# tft.net
KiCad netlist of a schematic drawn in EAGLE
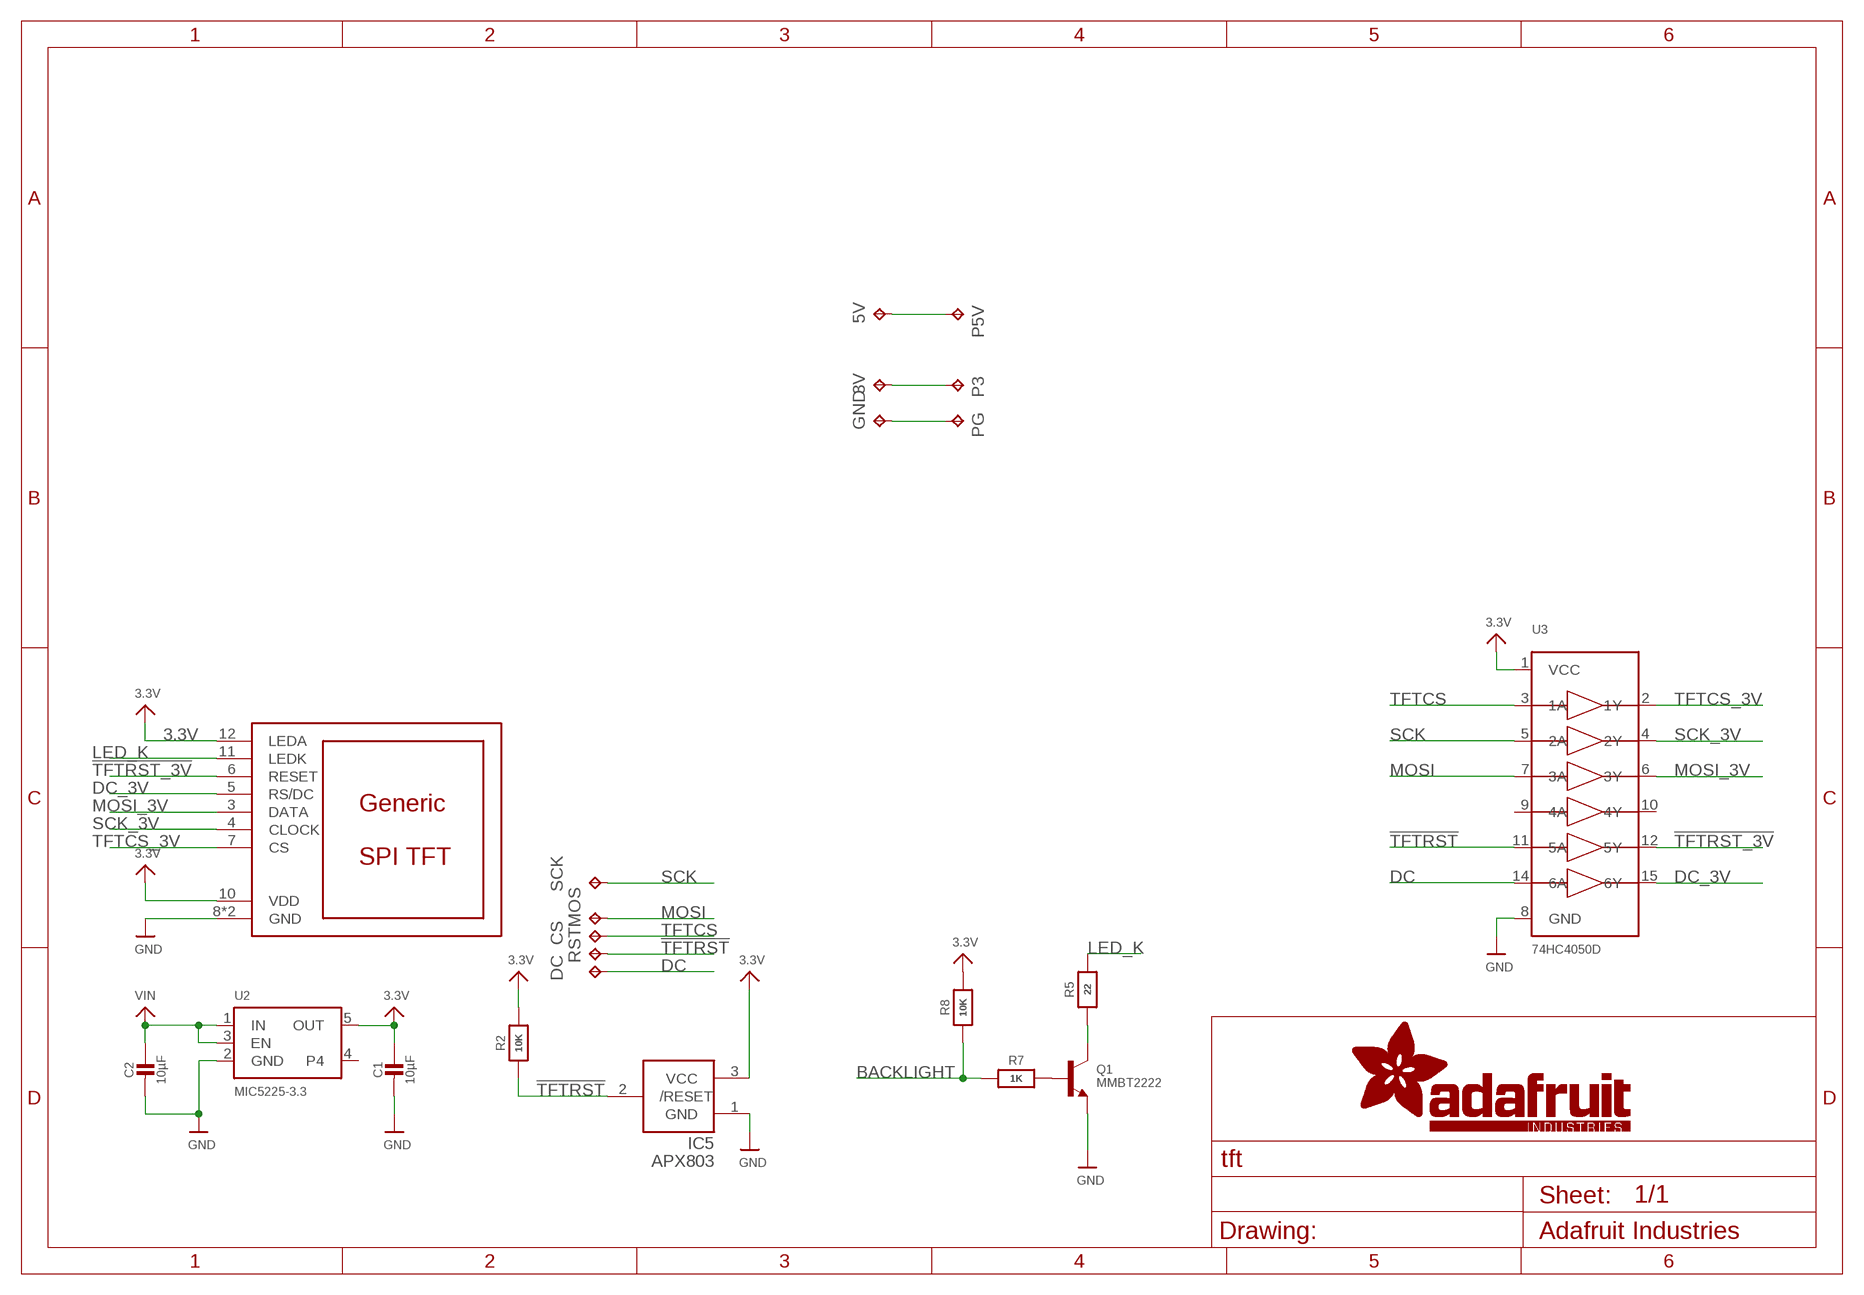
[diagram p0: schematic, sheet 1]

(export (version "E")
  (design (tool "Eeschema 10.0.6"))
  (components
    (comp (ref "3V")
      (value "TPB1,27")
      (footprint "eagle-import:B1,27")
      (libsource (lib "eagle-import") (part "TPB1,27"))
    )
    (comp (ref "5V")
      (value "TPB1,27")
      (footprint "eagle-import:B1,27")
      (libsource (lib "eagle-import") (part "TPB1,27"))
    )
    (comp (ref "C1")
      (value "10µF")
      (footprint "eagle-import:0805-NO")
      (libsource (lib "eagle-import") (part "CAP_CERAMIC0805-NOOUTLINE"))
    )
    (comp (ref "C2")
      (value "10µF")
      (footprint "eagle-import:0805-NO")
      (libsource (lib "eagle-import") (part "CAP_CERAMIC0805-NOOUTLINE"))
    )
    (comp (ref "CS")
      (value "TPB1,27")
      (footprint "eagle-import:B1,27")
      (libsource (lib "eagle-import") (part "TPB1,27"))
    )
    (comp (ref "DC")
      (value "TPB1,27")
      (footprint "eagle-import:B1,27")
      (libsource (lib "eagle-import") (part "TPB1,27"))
    )
    (comp (ref "DISP1")
      (value "DISP_LCD_GENERIC_SPI_1.14IN_240X135_WRAPUNDER")
      (footprint "eagle-import:TFT_1.14IN_240X135_WRAPUNDER")
      (libsource (lib "eagle-import") (part "DISP_LCD_GENERIC_SPI_1.14IN_240X135_WRAPUNDER"))
    )
    (comp (ref "GND")
      (value "TPB1,27")
      (footprint "eagle-import:B1,27")
      (libsource (lib "eagle-import") (part "TPB1,27"))
    )
    (comp (ref "IC5")
      (value "APX803")
      (footprint "eagle-import:SOT23")
      (libsource (lib "eagle-import") (part "AXP083-SAG"))
    )
    (comp (ref "MOS")
      (value "TPB1,27")
      (footprint "eagle-import:B1,27")
      (libsource (lib "eagle-import") (part "TPB1,27"))
    )
    (comp (ref "P3")
      (value "TPB1,27")
      (footprint "eagle-import:B1,27")
      (libsource (lib "eagle-import") (part "TPB1,27"))
    )
    (comp (ref "P5V")
      (value "TPB1,27")
      (footprint "eagle-import:B1,27")
      (libsource (lib "eagle-import") (part "TPB1,27"))
    )
    (comp (ref "PG")
      (value "TPB1,27")
      (footprint "eagle-import:B1,27")
      (libsource (lib "eagle-import") (part "TPB1,27"))
    )
    (comp (ref "Q1")
      (value "MMBT2222")
      (footprint "eagle-import:SOT23-WIDE")
      (libsource (lib "eagle-import") (part "TRANSISTOR_NPNWIDE"))
    )
    (comp (ref "R2")
      (value "10K")
      (footprint "eagle-import:0603-NO")
      (libsource (lib "eagle-import") (part "RESISTOR_0603_NOOUT"))
    )
    (comp (ref "R5")
      (value "22")
      (footprint "eagle-import:0603-NO")
      (libsource (lib "eagle-import") (part "RESISTOR_0603_NOOUT"))
    )
    (comp (ref "R7")
      (value "1K")
      (footprint "eagle-import:0603-NO")
      (libsource (lib "eagle-import") (part "RESISTOR_0603_NOOUT"))
    )
    (comp (ref "R8")
      (value "10K")
      (footprint "eagle-import:0603-NO")
      (libsource (lib "eagle-import") (part "RESISTOR_0603_NOOUT"))
    )
    (comp (ref "RST")
      (value "TPB1,27")
      (footprint "eagle-import:B1,27")
      (libsource (lib "eagle-import") (part "TPB1,27"))
    )
    (comp (ref "SCK")
      (value "TPB1,27")
      (footprint "eagle-import:B1,27")
      (libsource (lib "eagle-import") (part "TPB1,27"))
    )
    (comp (ref "U2")
      (value "MIC5225-3.3")
      (footprint "eagle-import:SOT23-5")
      (libsource (lib "eagle-import") (part "VREG_SOT23-5"))
    )
    (comp (ref "U3")
      (value "74HC4050D")
      (footprint "eagle-import:SOIC16")
      (libsource (lib "eagle-import") (part "74HC4050D"))
    )
  )
  (nets
    (net (code "1") (name "/BACKLIGHT") (class "Default")
      (node (ref "R7") (pin "1") (pinfunction "1_1") (pintype "passive"))
      (node (ref "R8") (pin "1") (pinfunction "1_1") (pintype "passive"))
    )
    (net (code "2") (name "/DC") (class "Default")
      (node (ref "DC") (pin "TP") (pinfunction "TP_TP") (pintype "input"))
      (node (ref "U3") (pin "14") (pinfunction "6A_14") (pintype "bidirectional"))
    )
    (net (code "3") (name "/DC_3V") (class "Default")
      (node (ref "DISP1") (pin "5") (pinfunction "RS/DC_5") (pintype "input"))
      (node (ref "U3") (pin "15") (pinfunction "6Y_15") (pintype "bidirectional"))
    )
    (net (code "4") (name "/LED_K") (class "Default")
      (node (ref "DISP1") (pin "11") (pinfunction "LEDK_11") (pintype "input"))
      (node (ref "R5") (pin "2") (pinfunction "2_2") (pintype "passive"))
    )
    (net (code "5") (name "/MOSI") (class "Default")
      (node (ref "MOS") (pin "TP") (pinfunction "TP_TP") (pintype "input"))
      (node (ref "U3") (pin "7") (pinfunction "3A_7") (pintype "bidirectional"))
    )
    (net (code "6") (name "/MOSI_3V") (class "Default")
      (node (ref "DISP1") (pin "3") (pinfunction "DATA_3") (pintype "bidirectional"))
      (node (ref "U3") (pin "6") (pinfunction "3Y_6") (pintype "bidirectional"))
    )
    (net (code "7") (name "/SCK") (class "Default")
      (node (ref "SCK") (pin "TP") (pinfunction "TP_TP") (pintype "input"))
      (node (ref "U3") (pin "5") (pinfunction "2A_5") (pintype "bidirectional"))
    )
    (net (code "8") (name "/SCK_3V") (class "Default")
      (node (ref "DISP1") (pin "4") (pinfunction "CLOCK_4") (pintype "input"))
      (node (ref "U3") (pin "4") (pinfunction "2Y_4") (pintype "bidirectional"))
    )
    (net (code "9") (name "/TFTCS") (class "Default")
      (node (ref "CS") (pin "TP") (pinfunction "TP_TP") (pintype "input"))
      (node (ref "U3") (pin "3") (pinfunction "1A_3") (pintype "bidirectional"))
    )
    (net (code "10") (name "/TFTCS_3V") (class "Default")
      (node (ref "DISP1") (pin "7") (pinfunction "CS_7") (pintype "input"))
      (node (ref "U3") (pin "2") (pinfunction "1Y_2") (pintype "bidirectional"))
    )
    (net (code "11") (name "/~{TFTRST_3V}") (class "Default")
      (node (ref "DISP1") (pin "6") (pinfunction "RESET_6") (pintype "input"))
      (node (ref "U3") (pin "12") (pinfunction "5Y_12") (pintype "bidirectional"))
    )
    (net (code "12") (name "/~{TFTRST}") (class "Default")
      (node (ref "IC5") (pin "2") (pinfunction "/RESET_2") (pintype "output"))
      (node (ref "R2") (pin "1") (pinfunction "1_1") (pintype "passive"))
      (node (ref "RST") (pin "TP") (pinfunction "TP_TP") (pintype "input"))
      (node (ref "U3") (pin "11") (pinfunction "5A_11") (pintype "bidirectional"))
    )
    (net (code "13") (name "3.3V") (class "Default")
      (node (ref "C1") (pin "1") (pinfunction "1_1") (pintype "passive"))
      (node (ref "DISP1") (pin "10") (pinfunction "VDD_10") (pintype "power_in"))
      (node (ref "DISP1") (pin "12") (pinfunction "LEDA_12") (pintype "input"))
      (node (ref "IC5") (pin "3") (pinfunction "VCC_3") (pintype "power_in"))
      (node (ref "R2") (pin "2") (pinfunction "2_2") (pintype "passive"))
      (node (ref "R8") (pin "2") (pinfunction "2_2") (pintype "passive"))
      (node (ref "U2") (pin "5") (pinfunction "OUT_5") (pintype "power_in"))
      (node (ref "U3") (pin "1") (pinfunction "VCC_1") (pintype "bidirectional"))
    )
    (net (code "14") (name "GND") (class "Default")
      (node (ref "C1") (pin "2") (pinfunction "2_2") (pintype "passive"))
      (node (ref "C2") (pin "2") (pinfunction "2_2") (pintype "passive"))
      (node (ref "DISP1") (pin "13") (pinfunction "GND_13") (pintype "power_in"))
      (node (ref "DISP1") (pin "8") (pinfunction "GND_8") (pintype "power_in"))
      (node (ref "GND") (pin "TP") (pinfunction "TP_TP") (pintype "input"))
      (node (ref "IC5") (pin "1") (pinfunction "GND_1") (pintype "power_in"))
      (node (ref "PG") (pin "TP") (pinfunction "TP_TP") (pintype "input"))
      (node (ref "Q1") (pin "2") (pinfunction "E_2") (pintype "passive"))
      (node (ref "U2") (pin "2") (pinfunction "GND_2") (pintype "power_in"))
      (node (ref "U3") (pin "8") (pinfunction "GND_8") (pintype "bidirectional"))
    )
    (net (code "15") (name "Net-(5V-PadTP)") (class "Default")
      (node (ref "5V") (pin "TP") (pinfunction "TP_TP") (pintype "input"))
      (node (ref "P5V") (pin "TP") (pinfunction "TP_TP") (pintype "input"))
    )
    (net (code "16") (name "Net-(Q1-B)") (class "Default")
      (node (ref "Q1") (pin "1") (pinfunction "B_1") (pintype "passive"))
      (node (ref "R7") (pin "2") (pinfunction "2_2") (pintype "passive"))
    )
    (net (code "17") (name "Net-(Q1-C)") (class "Default")
      (node (ref "Q1") (pin "3") (pinfunction "C_3") (pintype "passive"))
      (node (ref "R5") (pin "1") (pinfunction "1_1") (pintype "passive"))
    )
    (net (code "18") (name "VIN") (class "Default")
      (node (ref "3V") (pin "TP") (pinfunction "TP_TP") (pintype "input"))
      (node (ref "C2") (pin "1") (pinfunction "1_1") (pintype "passive"))
      (node (ref "P3") (pin "TP") (pinfunction "TP_TP") (pintype "input"))
      (node (ref "U2") (pin "1") (pinfunction "IN_1") (pintype "power_in"))
      (node (ref "U2") (pin "3") (pinfunction "EN_3") (pintype "input"))
    )
    (net (code "19") (name "unconnected-(U2-P4-Pad4)") (class "Default")
      (node (ref "U2") (pin "4") (pinfunction "P4_4") (pintype "bidirectional"))
    )
    (net (code "20") (name "unconnected-(U3-4A-Pad9)") (class "Default")
      (node (ref "U3") (pin "9") (pinfunction "4A_9") (pintype "bidirectional"))
    )
    (net (code "21") (name "unconnected-(U3-4Y-Pad10)") (class "Default")
      (node (ref "U3") (pin "10") (pinfunction "4Y_10") (pintype "bidirectional"))
    )
  )
)
